# Board_V02.net
KiCad netlist of a schematic drawn in EAGLE
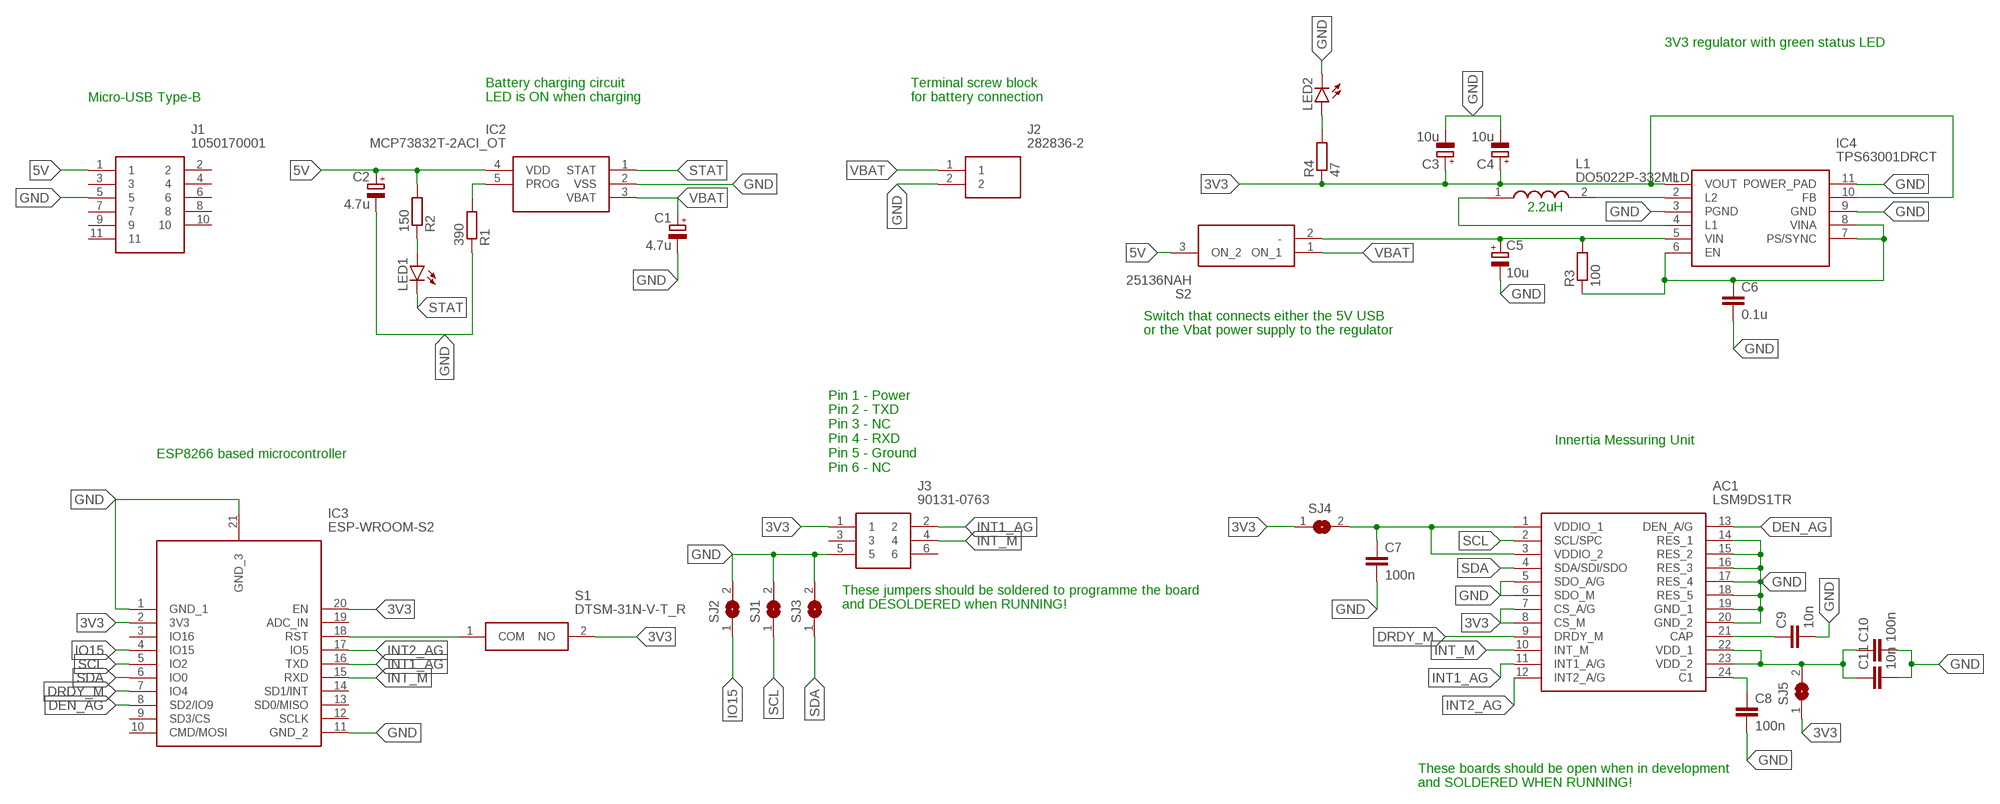
[diagram p0: schematic, sheet 1]

(export (version "E")
  (design (tool "Eeschema 10.0.6"))
  (components
    (comp (ref "AC1")
      (value "LSM9DS1TR")
      (footprint "eagle-import:LGA-24L(3X3.5X1MM)")
      (fields (field (name "MOUSER_PART_NUMBER") "511-LSM9DS1TR") (field (name "RS_PART_NUMBER") "1660908"))
      (libsource (lib "eagle-import") (part "LSM9DS1TR"))
    )
    (comp (ref "C1")
      (value "4.7u")
      (footprint "eagle-import:D_7343-31R")
      (libsource (lib "eagle-import") (part "CPOL-EUD/7343-31R"))
    )
    (comp (ref "C2")
      (value "4.7u")
      (footprint "eagle-import:D_7343-31R")
      (libsource (lib "eagle-import") (part "CPOL-EUD/7343-31R"))
    )
    (comp (ref "C3")
      (value "10u")
      (footprint "eagle-import:D_7343-31R")
      (libsource (lib "eagle-import") (part "CPOL-EUD/7343-31R"))
    )
    (comp (ref "C4")
      (value "10u")
      (footprint "eagle-import:D_7343-31R")
      (libsource (lib "eagle-import") (part "CPOL-EUD/7343-31R"))
    )
    (comp (ref "C5")
      (value "10u")
      (footprint "eagle-import:D_7343-31R")
      (libsource (lib "eagle-import") (part "CPOL-EUD/7343-31R"))
    )
    (comp (ref "C6")
      (value "0.1u")
      (footprint "eagle-import:C0402")
      (libsource (lib "eagle-import") (part "C-EUC0402"))
    )
    (comp (ref "C7")
      (value "100n")
      (footprint "eagle-import:C0805")
      (libsource (lib "eagle-import") (part "C-EUC0805"))
    )
    (comp (ref "C8")
      (value "100n")
      (footprint "eagle-import:C0805")
      (libsource (lib "eagle-import") (part "C-EUC0805"))
    )
    (comp (ref "C9")
      (value "10n")
      (footprint "eagle-import:C0805")
      (libsource (lib "eagle-import") (part "C-EUC0805"))
    )
    (comp (ref "C10")
      (value "100n")
      (footprint "eagle-import:C0805")
      (libsource (lib "eagle-import") (part "C-EUC0805"))
    )
    (comp (ref "C11")
      (value "10n")
      (footprint "eagle-import:C0805")
      (libsource (lib "eagle-import") (part "C-EUC0805"))
    )
    (comp (ref "IC2")
      (value "MCP73832T-2ACI_OT")
      (footprint "eagle-import:SOT95P270X145-5N")
      (fields
        (field (name "MANUFACTURER_PART_NUMBER") "MCP73832T-2ACI/OT")
        (field (name "MOUSER_PART_NUMBER") "579-MCP73832T-2ACIOT")
        (field (name "RS_PART_NUMBER") "9122897")
      )
      (libsource (lib "eagle-import") (part "MCP73832T-2ACI_OT"))
    )
    (comp (ref "IC3")
      (value "ESP-WROOM-S2")
      (footprint "eagle-import:QFN150P1600X1700X315-21N")
      (libsource (lib "eagle-import") (part "ESP-WROOM-S2"))
    )
    (comp (ref "IC4")
      (value "TPS63001DRCT")
      (footprint "eagle-import:SON50P300X300X100-11N")
      (fields (field (name "RS_PART_NUMBER") "7968405"))
      (libsource (lib "eagle-import") (part "TPS63001DRCT"))
    )
    (comp (ref "J1")
      (value "1050170001")
      (footprint "eagle-import:MICROUSB-BTYPE")
      (libsource (lib "eagle-import") (part "1050170001"))
    )
    (comp (ref "J2")
      (value "282836-2")
      (footprint "eagle-import:SHDR2W100P0X500_1X2_1000X820X1")
      (fields (field (name "MOUSER_PART_NUMBER") "571-2828362") (field (name "RS_PART_NUMBER") "1354983"))
      (libsource (lib "eagle-import") (part "282836-2"))
    )
    (comp (ref "J3")
      (value "90131-0763")
      (footprint "eagle-import:HDRV6W90P254_2X3_762X500X560P")
      (fields (field (name "MOUSER_PART_NUMBER") "538-90131-0763") (field (name "RS_PART_NUMBER") "3606443P"))
      (libsource (lib "eagle-import") (part "90131-0763"))
    )
    (comp (ref "L1")
      (value "DO5022P-332MLD")
      (footprint "eagle-import:DO5022P-104MLD")
      (fields (field (name "MOUSER_PART_NUMBER") "994-DO5022P-332MLD"))
      (libsource (lib "eagle-import") (part "DO5022P-332MLD"))
    )
    (comp (ref "LED1")
      (value "LED5MM")
      (footprint "eagle-import:LED5MM")
      (libsource (lib "eagle-import") (part "LED5MM"))
    )
    (comp (ref "LED2")
      (value "LED5MM")
      (footprint "eagle-import:LED5MM")
      (libsource (lib "eagle-import") (part "LED5MM"))
    )
    (comp (ref "R1")
      (value "390")
      (footprint "eagle-import:R0805")
      (libsource (lib "eagle-import") (part "R-EU_R0805"))
    )
    (comp (ref "R2")
      (value "150")
      (footprint "eagle-import:R0805")
      (libsource (lib "eagle-import") (part "R-EU_R0805"))
    )
    (comp (ref "R3")
      (value "100")
      (footprint "eagle-import:R0805")
      (libsource (lib "eagle-import") (part "R-EU_R0805"))
    )
    (comp (ref "R4")
      (value "47")
      (footprint "eagle-import:R0805")
      (libsource (lib "eagle-import") (part "R-EU_R0805"))
    )
    (comp (ref "S1")
      (value "DTSM-31N-V-T_R")
      (footprint "eagle-import:DTSM32NVTR")
      (fields
        (field (name "MANUFACTURER_PART_NUMBER") "DTSM-31N-V-T/R")
        (field (name "MOUSER_PART_NUMBER") "113-DTSM31NVTR")
      )
      (libsource (lib "eagle-import") (part "DTSM-31N-V-T_R"))
    )
    (comp (ref "S2")
      (value "25136NAH")
      (footprint "eagle-import:25136NAH")
      (fields (field (name "MOUSER_PART_NUMBER") "642-25136NAH") (field (name "RS_PART_NUMBER") "0339673A"))
      (libsource (lib "eagle-import") (part "25136NAH"))
    )
    (comp (ref "SJ1")
      (value "SJW")
      (footprint "eagle-import:SJW")
      (libsource (lib "eagle-import") (part "SJW"))
    )
    (comp (ref "SJ2")
      (value "SJW")
      (footprint "eagle-import:SJW")
      (libsource (lib "eagle-import") (part "SJW"))
    )
    (comp (ref "SJ3")
      (value "SJW")
      (footprint "eagle-import:SJW")
      (libsource (lib "eagle-import") (part "SJW"))
    )
    (comp (ref "SJ4")
      (value "SJW")
      (footprint "eagle-import:SJW")
      (libsource (lib "eagle-import") (part "SJW"))
    )
    (comp (ref "SJ5")
      (value "SJW")
      (footprint "eagle-import:SJW")
      (libsource (lib "eagle-import") (part "SJW"))
    )
  )
  (nets
    (net (code "1") (name "3V3") (class "Default")
      (node (ref "AC1") (pin "7") (pinfunction "CS_A/G_7") (pintype "bidirectional"))
      (node (ref "AC1") (pin "8") (pinfunction "CS_M_8") (pintype "bidirectional"))
      (node (ref "C3") (pin "+") (pinfunction "+_+") (pintype "passive"))
      (node (ref "C4") (pin "+") (pinfunction "+_+") (pintype "passive"))
      (node (ref "IC3") (pin "2") (pinfunction "3V3_2") (pintype "power_in"))
      (node (ref "IC3") (pin "20") (pinfunction "EN_20") (pintype "bidirectional"))
      (node (ref "IC4") (pin "1") (pinfunction "VOUT_1") (pintype "bidirectional"))
      (node (ref "IC4") (pin "10") (pinfunction "FB_10") (pintype "bidirectional"))
      (node (ref "J3") (pin "1") (pinfunction "1_1") (pintype "bidirectional"))
      (node (ref "R4") (pin "1") (pinfunction "1_1") (pintype "passive"))
      (node (ref "S1") (pin "2") (pinfunction "NO_2") (pintype "bidirectional"))
      (node (ref "SJ4") (pin "1") (pinfunction "1_1") (pintype "passive"))
      (node (ref "SJ5") (pin "1") (pinfunction "1_1") (pintype "passive"))
    )
    (net (code "2") (name "5V") (class "Default")
      (node (ref "C2") (pin "+") (pinfunction "+_+") (pintype "passive"))
      (node (ref "IC2") (pin "4") (pinfunction "VDD_4") (pintype "power_in"))
      (node (ref "J1") (pin "1") (pinfunction "1_1") (pintype "bidirectional"))
      (node (ref "R2") (pin "2") (pinfunction "2_2") (pintype "passive"))
      (node (ref "S2") (pin "3") (pinfunction "ON_2_3") (pintype "bidirectional"))
    )
    (net (code "3") (name "DEN_AG") (class "Default")
      (node (ref "AC1") (pin "13") (pinfunction "DEN_A/G_13") (pintype "bidirectional"))
      (node (ref "IC3") (pin "8") (pinfunction "SD2/IO9_8") (pintype "bidirectional"))
    )
    (net (code "4") (name "DRDY_M") (class "Default")
      (node (ref "AC1") (pin "9") (pinfunction "DRDY_M_9") (pintype "bidirectional"))
      (node (ref "IC3") (pin "7") (pinfunction "IO4_7") (pintype "bidirectional"))
    )
    (net (code "5") (name "GND") (class "Default")
      (node (ref "AC1") (pin "14") (pinfunction "RES_1_14") (pintype "power_in"))
      (node (ref "AC1") (pin "15") (pinfunction "RES_2_15") (pintype "power_in"))
      (node (ref "AC1") (pin "16") (pinfunction "RES_3_16") (pintype "power_in"))
      (node (ref "AC1") (pin "17") (pinfunction "RES_4_17") (pintype "power_in"))
      (node (ref "AC1") (pin "18") (pinfunction "RES_5_18") (pintype "power_in"))
      (node (ref "AC1") (pin "19") (pinfunction "GND_1_19") (pintype "power_in"))
      (node (ref "AC1") (pin "20") (pinfunction "GND_2_20") (pintype "power_in"))
      (node (ref "AC1") (pin "5") (pinfunction "SDO_A/G_5") (pintype "output"))
      (node (ref "AC1") (pin "6") (pinfunction "SDO_M_6") (pintype "output"))
      (node (ref "C1") (pin "-") (pinfunction "-_-") (pintype "passive"))
      (node (ref "C10") (pin "2") (pinfunction "2_2") (pintype "passive"))
      (node (ref "C11") (pin "2") (pinfunction "2_2") (pintype "passive"))
      (node (ref "C2") (pin "-") (pinfunction "-_-") (pintype "passive"))
      (node (ref "C3") (pin "-") (pinfunction "-_-") (pintype "passive"))
      (node (ref "C4") (pin "-") (pinfunction "-_-") (pintype "passive"))
      (node (ref "C5") (pin "-") (pinfunction "-_-") (pintype "passive"))
      (node (ref "C6") (pin "2") (pinfunction "2_2") (pintype "passive"))
      (node (ref "C7") (pin "2") (pinfunction "2_2") (pintype "passive"))
      (node (ref "C8") (pin "2") (pinfunction "2_2") (pintype "passive"))
      (node (ref "C9") (pin "2") (pinfunction "2_2") (pintype "passive"))
      (node (ref "IC2") (pin "2") (pinfunction "VSS_2") (pintype "power_in"))
      (node (ref "IC3") (pin "1") (pinfunction "GND_1_1") (pintype "power_in"))
      (node (ref "IC3") (pin "11") (pinfunction "GND_2_11") (pintype "power_in"))
      (node (ref "IC3") (pin "21") (pinfunction "GND_3_21") (pintype "power_in"))
      (node (ref "IC4") (pin "11") (pinfunction "POWER_PAD_11") (pintype "bidirectional"))
      (node (ref "IC4") (pin "3") (pinfunction "PGND_3") (pintype "bidirectional"))
      (node (ref "IC4") (pin "9") (pinfunction "GND_9") (pintype "bidirectional"))
      (node (ref "J1") (pin "5") (pinfunction "5_5") (pintype "bidirectional"))
      (node (ref "J2") (pin "2") (pinfunction "2_2") (pintype "bidirectional"))
      (node (ref "J3") (pin "5") (pinfunction "5_5") (pintype "bidirectional"))
      (node (ref "LED2") (pin "K") (pinfunction "C_K") (pintype "passive"))
      (node (ref "R1") (pin "1") (pinfunction "1_1") (pintype "passive"))
      (node (ref "SJ1") (pin "2") (pinfunction "2_2") (pintype "passive"))
      (node (ref "SJ2") (pin "2") (pinfunction "2_2") (pintype "passive"))
      (node (ref "SJ3") (pin "2") (pinfunction "2_2") (pintype "passive"))
    )
    (net (code "6") (name "INT1_AG") (class "Default")
      (node (ref "AC1") (pin "11") (pinfunction "INT1_A/G_11") (pintype "bidirectional"))
      (node (ref "IC3") (pin "16") (pinfunction "TXD_16") (pintype "bidirectional"))
      (node (ref "J3") (pin "2") (pinfunction "2_2") (pintype "bidirectional"))
    )
    (net (code "7") (name "INT2_AG") (class "Default")
      (node (ref "AC1") (pin "12") (pinfunction "INT2_A/G_12") (pintype "bidirectional"))
      (node (ref "IC3") (pin "17") (pinfunction "IO5_17") (pintype "bidirectional"))
    )
    (net (code "8") (name "INT_M") (class "Default")
      (node (ref "AC1") (pin "10") (pinfunction "INT_M_10") (pintype "bidirectional"))
      (node (ref "IC3") (pin "15") (pinfunction "RXD_15") (pintype "bidirectional"))
      (node (ref "J3") (pin "4") (pinfunction "4_4") (pintype "bidirectional"))
    )
    (net (code "9") (name "IO15") (class "Default")
      (node (ref "IC3") (pin "4") (pinfunction "IO15_4") (pintype "bidirectional"))
      (node (ref "SJ2") (pin "1") (pinfunction "1_1") (pintype "passive"))
    )
    (net (code "10") (name "Net-(AC1-C1)") (class "Default")
      (node (ref "AC1") (pin "24") (pinfunction "C1_24") (pintype "bidirectional"))
      (node (ref "C8") (pin "1") (pinfunction "1_1") (pintype "passive"))
    )
    (net (code "11") (name "Net-(AC1-CAP)") (class "Default")
      (node (ref "AC1") (pin "21") (pinfunction "CAP_21") (pintype "power_in"))
      (node (ref "C9") (pin "1") (pinfunction "1_1") (pintype "passive"))
    )
    (net (code "12") (name "Net-(AC1-VDDIO_1)") (class "Default")
      (node (ref "AC1") (pin "1") (pinfunction "VDDIO_1_1") (pintype "power_in"))
      (node (ref "AC1") (pin "3") (pinfunction "VDDIO_2_3") (pintype "power_in"))
      (node (ref "C7") (pin "1") (pinfunction "1_1") (pintype "passive"))
      (node (ref "SJ4") (pin "2") (pinfunction "2_2") (pintype "passive"))
    )
    (net (code "13") (name "Net-(AC1-VDD_1)") (class "Default")
      (node (ref "AC1") (pin "22") (pinfunction "VDD_1_22") (pintype "power_in"))
      (node (ref "AC1") (pin "23") (pinfunction "VDD_2_23") (pintype "power_in"))
      (node (ref "C10") (pin "1") (pinfunction "1_1") (pintype "passive"))
      (node (ref "C11") (pin "1") (pinfunction "1_1") (pintype "passive"))
      (node (ref "SJ5") (pin "2") (pinfunction "2_2") (pintype "passive"))
    )
    (net (code "14") (name "Net-(IC2-PROG)") (class "Default")
      (node (ref "IC2") (pin "5") (pinfunction "PROG_5") (pintype "bidirectional"))
      (node (ref "R1") (pin "2") (pinfunction "2_2") (pintype "passive"))
    )
    (net (code "15") (name "Net-(IC3-RST)") (class "Default")
      (node (ref "IC3") (pin "18") (pinfunction "RST_18") (pintype "input"))
      (node (ref "S1") (pin "1") (pinfunction "COM_1") (pintype "bidirectional"))
    )
    (net (code "16") (name "Net-(IC4-EN)") (class "Default")
      (node (ref "C6") (pin "1") (pinfunction "1_1") (pintype "passive"))
      (node (ref "IC4") (pin "6") (pinfunction "EN_6") (pintype "bidirectional"))
      (node (ref "IC4") (pin "7") (pinfunction "PS/SYNC_7") (pintype "bidirectional"))
      (node (ref "IC4") (pin "8") (pinfunction "VINA_8") (pintype "bidirectional"))
      (node (ref "R3") (pin "1") (pinfunction "1_1") (pintype "passive"))
    )
    (net (code "17") (name "Net-(IC4-L1)") (class "Default")
      (node (ref "IC4") (pin "4") (pinfunction "L1_4") (pintype "bidirectional"))
      (node (ref "L1") (pin "1") (pinfunction "1_1") (pintype "bidirectional"))
    )
    (net (code "18") (name "Net-(IC4-L2)") (class "Default")
      (node (ref "IC4") (pin "2") (pinfunction "L2_2") (pintype "bidirectional"))
      (node (ref "L1") (pin "2") (pinfunction "2_2") (pintype "bidirectional"))
    )
    (net (code "19") (name "Net-(IC4-VIN)") (class "Default")
      (node (ref "C5") (pin "+") (pinfunction "+_+") (pintype "passive"))
      (node (ref "IC4") (pin "5") (pinfunction "VIN_5") (pintype "bidirectional"))
      (node (ref "R3") (pin "2") (pinfunction "2_2") (pintype "passive"))
      (node (ref "S2") (pin "2") (pinfunction "-_2") (pintype "bidirectional"))
    )
    (net (code "20") (name "Net-(LED1-PadA)") (class "Default")
      (node (ref "LED1") (pin "A") (pinfunction "A_A") (pintype "passive"))
      (node (ref "R2") (pin "1") (pinfunction "1_1") (pintype "passive"))
    )
    (net (code "21") (name "Net-(LED2-PadA)") (class "Default")
      (node (ref "LED2") (pin "A") (pinfunction "A_A") (pintype "passive"))
      (node (ref "R4") (pin "2") (pinfunction "2_2") (pintype "passive"))
    )
    (net (code "22") (name "SCL") (class "Default")
      (node (ref "AC1") (pin "2") (pinfunction "SCL/SPC_2") (pintype "output"))
      (node (ref "IC3") (pin "5") (pinfunction "IO2_5") (pintype "bidirectional"))
      (node (ref "SJ1") (pin "1") (pinfunction "1_1") (pintype "passive"))
    )
    (net (code "23") (name "SDA") (class "Default")
      (node (ref "AC1") (pin "4") (pinfunction "SDA/SDI/SDO_4") (pintype "bidirectional"))
      (node (ref "IC3") (pin "6") (pinfunction "IO0_6") (pintype "bidirectional"))
      (node (ref "SJ3") (pin "1") (pinfunction "1_1") (pintype "passive"))
    )
    (net (code "24") (name "STAT") (class "Default")
      (node (ref "IC2") (pin "1") (pinfunction "STAT_1") (pintype "bidirectional"))
      (node (ref "LED1") (pin "K") (pinfunction "C_K") (pintype "passive"))
    )
    (net (code "25") (name "VBAT") (class "Default")
      (node (ref "C1") (pin "+") (pinfunction "+_+") (pintype "passive"))
      (node (ref "IC2") (pin "3") (pinfunction "VBAT_3") (pintype "bidirectional"))
      (node (ref "J2") (pin "1") (pinfunction "1_1") (pintype "bidirectional"))
      (node (ref "S2") (pin "1") (pinfunction "ON_1_1") (pintype "bidirectional"))
    )
    (net (code "26") (name "unconnected-(IC3-ADC_IN-Pad19)") (class "Default")
      (node (ref "IC3") (pin "19") (pinfunction "ADC_IN_19") (pintype "input"))
    )
    (net (code "27") (name "unconnected-(IC3-CMD{slash}MOSI-Pad10)") (class "Default")
      (node (ref "IC3") (pin "10") (pinfunction "CMD/MOSI_10") (pintype "bidirectional"))
    )
    (net (code "28") (name "unconnected-(IC3-IO16-Pad3)") (class "Default")
      (node (ref "IC3") (pin "3") (pinfunction "IO16_3") (pintype "bidirectional"))
    )
    (net (code "29") (name "unconnected-(IC3-SCLK-Pad12)") (class "Default")
      (node (ref "IC3") (pin "12") (pinfunction "SCLK_12") (pintype "bidirectional"))
    )
    (net (code "30") (name "unconnected-(IC3-SD0{slash}MISO-Pad13)") (class "Default")
      (node (ref "IC3") (pin "13") (pinfunction "SD0/MISO_13") (pintype "bidirectional"))
    )
    (net (code "31") (name "unconnected-(IC3-SD1{slash}INT-Pad14)") (class "Default")
      (node (ref "IC3") (pin "14") (pinfunction "SD1/INT_14") (pintype "bidirectional"))
    )
    (net (code "32") (name "unconnected-(IC3-SD3{slash}CS-Pad9)") (class "Default")
      (node (ref "IC3") (pin "9") (pinfunction "SD3/CS_9") (pintype "bidirectional"))
    )
    (net (code "33") (name "unconnected-(J1-Pad2)") (class "Default")
      (node (ref "J1") (pin "2") (pinfunction "2_2") (pintype "bidirectional"))
    )
    (net (code "34") (name "unconnected-(J1-Pad3)") (class "Default")
      (node (ref "J1") (pin "3") (pinfunction "3_3") (pintype "bidirectional"))
    )
    (net (code "35") (name "unconnected-(J1-Pad4)") (class "Default")
      (node (ref "J1") (pin "4") (pinfunction "4_4") (pintype "bidirectional"))
    )
    (net (code "36") (name "unconnected-(J1-Pad6)") (class "Default")
      (node (ref "J1") (pin "6") (pinfunction "6_6") (pintype "bidirectional"))
    )
    (net (code "37") (name "unconnected-(J1-Pad7)") (class "Default")
      (node (ref "J1") (pin "7") (pinfunction "7_7") (pintype "bidirectional"))
    )
    (net (code "38") (name "unconnected-(J1-Pad8)") (class "Default")
      (node (ref "J1") (pin "8") (pinfunction "8_8") (pintype "bidirectional"))
    )
    (net (code "39") (name "unconnected-(J1-Pad9)") (class "Default")
      (node (ref "J1") (pin "9") (pinfunction "9_9") (pintype "bidirectional"))
    )
    (net (code "40") (name "unconnected-(J1-Pad10)") (class "Default")
      (node (ref "J1") (pin "10") (pinfunction "10_10") (pintype "bidirectional"))
    )
    (net (code "41") (name "unconnected-(J1-Pad11)") (class "Default")
      (node (ref "J1") (pin "11") (pinfunction "11_11") (pintype "bidirectional"))
    )
    (net (code "42") (name "unconnected-(J3-Pad3)") (class "Default")
      (node (ref "J3") (pin "3") (pinfunction "3_3") (pintype "bidirectional"))
    )
    (net (code "43") (name "unconnected-(J3-Pad6)") (class "Default")
      (node (ref "J3") (pin "6") (pinfunction "6_6") (pintype "bidirectional"))
    )
  )
)
